# Pg4_Switches_Latches_Connectors.net
KiCad netlist of a schematic drawn in Altium Designer
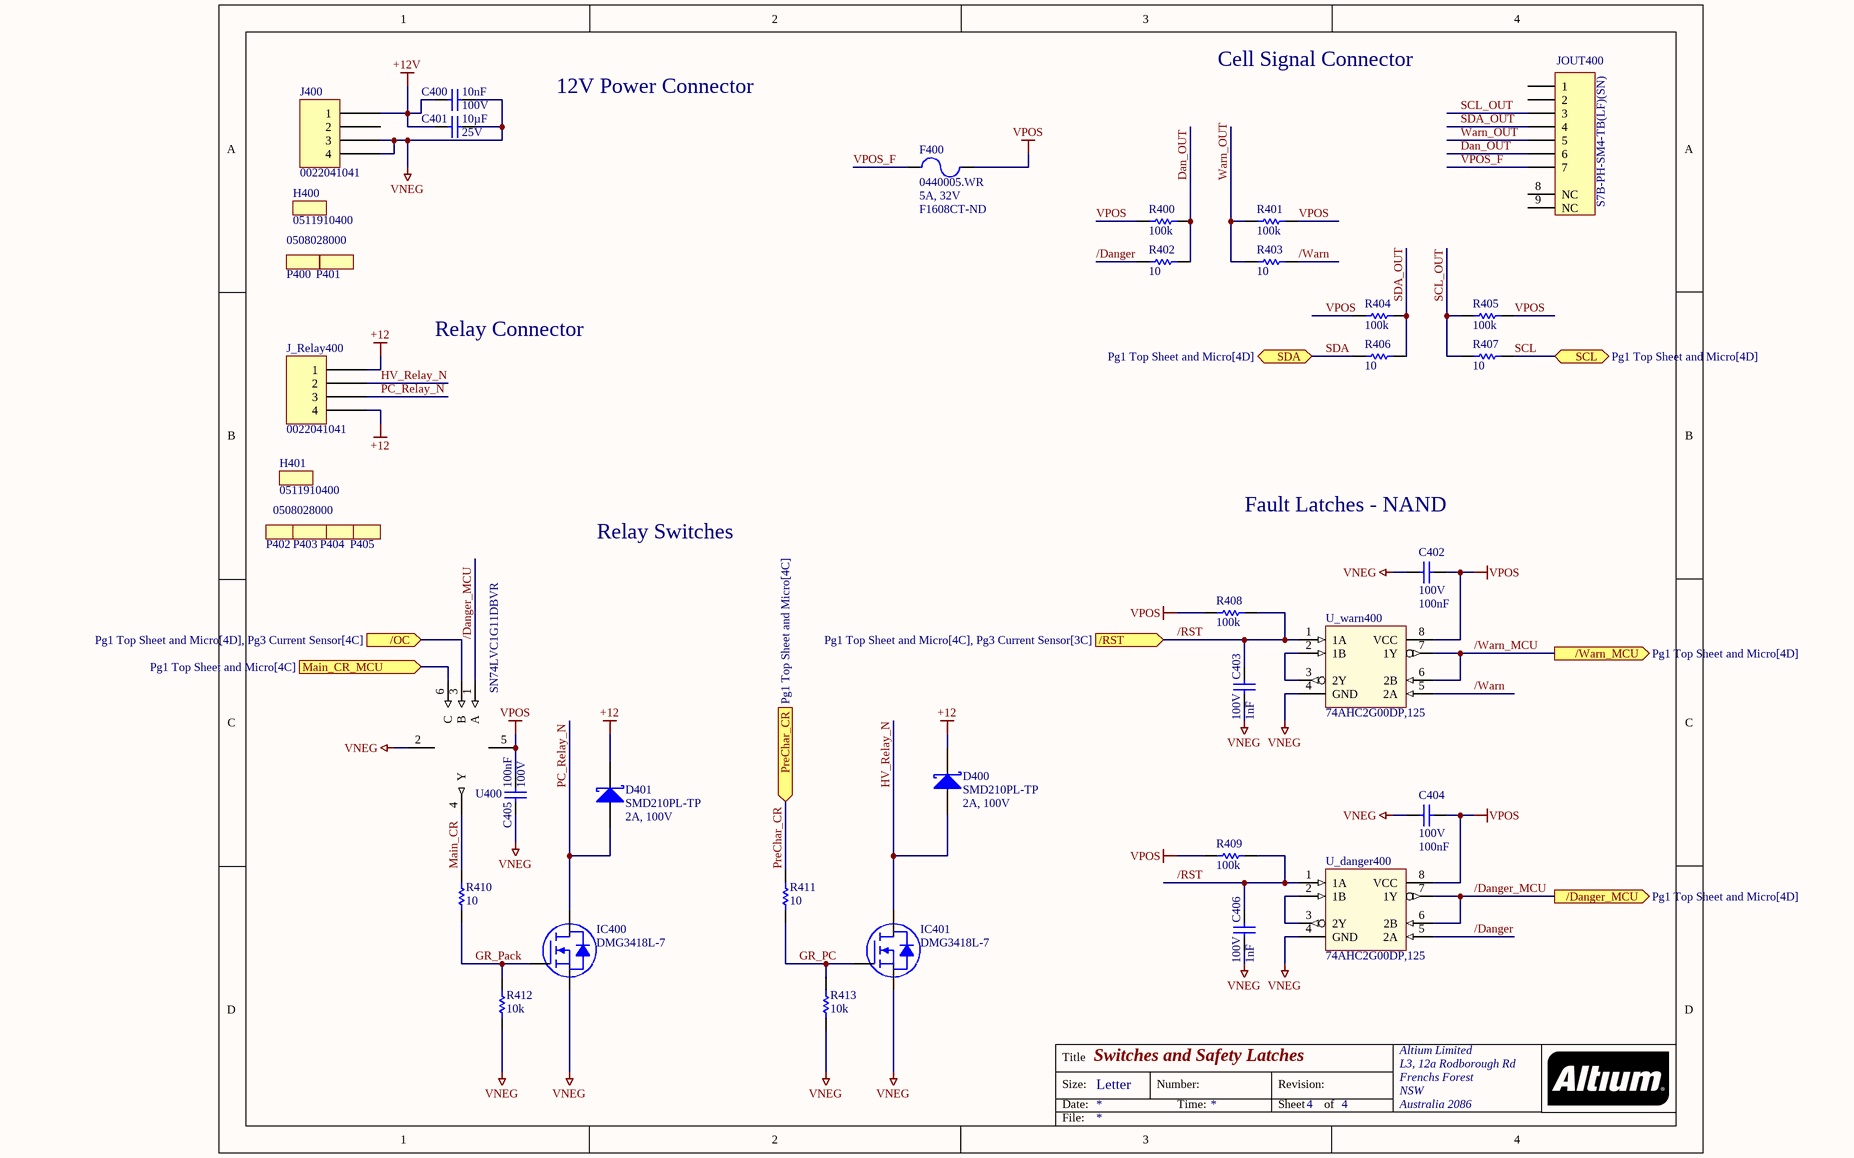
[diagram p0: Pg4 Switches, Latches, Connectors.SchDoc]

(export (version "E")
  (design (tool "Eeschema 10.0.6"))
  (components
    (comp (ref "C400")
      (value "10nF")
      (footprint "CAPC2012N")
      (description "Capacitor, Ceramic, 10nF, 100V, 0805, 10%, 125C")
      (fields (field (name "RATED") "100V") (field (name "Comment") "C0805C103K1RAC7025"))
      (libsource (lib "SchLib - EE391 Master") (part "C0805C103K1RAC7025"))
    )
    (comp (ref "C401")
      (value "10µF")
      (footprint "CAPC3225N")
      (description "Capacitor, Ceramic, 10µF, 25V, 0805, 10%, 125C")
      (fields (field (name "RATED") "25V") (field (name "Comment") "C1210C106K3RACAUTO"))
      (libsource (lib "SchLib - EE391 Master") (part "C1210C106K3RACAUTO"))
    )
    (comp (ref "C402")
      (value "100nF")
      (footprint "CAPC2012N")
      (description "Capacitor, Ceramic, 100nF, 25V, 0805, 10%, 125C")
      (fields (field (name "RATED") "100V") (field (name "Comment") "CL21B104KACNNNC"))
      (libsource (lib "SchLib - EE391 Master") (part "C0805C104K1RACAUTO"))
    )
    (comp (ref "C403")
      (value "1nF")
      (footprint "CAPC2012N")
      (description "Capacitor, Ceramic, 1nF, 100V, 0805, 10%, 125C")
      (fields (field (name "RATED") "100V") (field (name "Comment") "C0805C102K1RACAUTO"))
      (libsource (lib "SchLib - EE391 Master") (part "C0805C102K1RACAUTO"))
    )
    (comp (ref "C404")
      (value "100nF")
      (footprint "CAPC2012N")
      (description "Capacitor, Ceramic, 100nF, 25V, 0805, 10%, 125C")
      (fields (field (name "RATED") "100V") (field (name "Comment") "CL21B104KACNNNC"))
      (libsource (lib "SchLib - EE391 Master") (part "C0805C104K1RACAUTO"))
    )
    (comp (ref "C405")
      (value "100nF")
      (footprint "CAPC2012N")
      (description "Capacitor, Ceramic, 100nF, 25V, 0805, 10%, 125C")
      (fields (field (name "RATED") "100V") (field (name "Comment") "CL21B104KACNNNC"))
      (libsource (lib "SchLib - EE391 Master") (part "C0805C104K1RACAUTO"))
    )
    (comp (ref "C406")
      (value "1nF")
      (footprint "CAPC2012N")
      (description "Capacitor, Ceramic, 1nF, 100V, 0805, 10%, 125C")
      (fields (field (name "RATED") "100V") (field (name "Comment") "C0805C102K1RACAUTO"))
      (libsource (lib "SchLib - EE391 Master") (part "C0805C102K1RACAUTO"))
    )
    (comp (ref "D400")
      (value "SMD210PL-TP")
      (footprint "SOD123")
      (description "Diode, Si Sch, 100V, 2A, SOD123")
      (fields (field (name "RATED") "2A, 100V"))
      (libsource (lib "SchLib - EE391 Master") (part "SMD210PL"))
    )
    (comp (ref "D401")
      (value "SMD210PL-TP")
      (footprint "SOD123")
      (description "Diode, Si Sch, 100V, 2A, SOD123")
      (fields (field (name "RATED") "2A, 100V"))
      (libsource (lib "SchLib - EE391 Master") (part "SMD210PL"))
    )
    (comp (ref "F400")
      (value "0440005.WR")
      (footprint "CAPC1608N")
      (description "Fuse, SMT, 5A, 32VAC/VDC, 1206")
      (fields (field (name "RATED") "5A, 32V") (field (name "SUPPLIER PART NUMBER 1") "F1608CT-ND"))
      (libsource (lib "SchLib - EE391 Master") (part "0440005.WR"))
    )
    (comp (ref "H400")
      (value "0511910400")
      (description "Housing, Molex, Maiting Part 0511910400")
      (libsource (lib "Connectors") (part "0022041041(Housing)"))
    )
    (comp (ref "H401")
      (value "0511910400")
      (description "Housing, Molex, Maiting Part 0511910400")
      (libsource (lib "Connectors") (part "0022041041(Housing)"))
    )
    (comp (ref "IC400")
      (value "DMG3418L-7")
      (footprint "DIODES SOT-23-3")
      (description "MOSFET N-CH 30V 4A SOT23")
      (fields (field (name "MANUFACTURER") "Diodes Incorporated"))
      (libsource (lib "Celestial Altium Library - altium_library") (part "DIODES INC MOSFET N-CH SOT-23-3"))
    )
    (comp (ref "IC401")
      (value "DMG3418L-7")
      (footprint "DIODES SOT-23-3")
      (description "MOSFET N-CH 30V 4A SOT23")
      (fields (field (name "MANUFACTURER") "Diodes Incorporated"))
      (libsource (lib "Celestial Altium Library - altium_library") (part "DIODES INC MOSFET N-CH SOT-23-3"))
    )
    (comp (ref "J400")
      (value "0022041041")
      (footprint "0022041041")
      (description "Header, 4 pos, 2.5mm pitch, Molex\r\nKit Parts\r\nHousing: 0511910400\r\nTerminals: 0508028000")
      (libsource (lib "Connectors") (part "0022041041"))
    )
    (comp (ref "JOUT400")
      (value "S7B-PH-SM4-TB(LF)(SN)")
      (footprint "JST-PH-S7")
      (description "Header, JST, 7-Pin, Right-Angle, PH, Surface Mount")
      (libsource (lib "SchLib - EE391 Master") (part "S7B-PH-SM4-TB(LF)(SN)"))
    )
    (comp (ref "J_Relay400")
      (value "0022041041")
      (footprint "0022041041")
      (description "Header, 4 pos, 2.5mm pitch, Molex\r\nKit Parts\r\nHousing: 0511910400\r\nTerminals: 0508028000")
      (libsource (lib "Connectors") (part "0022041041"))
    )
    (comp (ref "P400")
      (value "0508028000")
      (description "Terminal, Molex, Maiting Part 0511910400")
      (libsource (lib "Connectors") (part "0022041041(Terminal)"))
    )
    (comp (ref "P401")
      (value "0508028000")
      (description "Terminal, Molex, Maiting Part 0511910400")
      (libsource (lib "") (part "0022041041(Terminal)_1"))
    )
    (comp (ref "P402")
      (value "0508028000")
      (description "Terminal, Molex, Maiting Part 0511910400")
      (libsource (lib "") (part "0022041041(Terminal)_1"))
    )
    (comp (ref "P403")
      (value "0508028000")
      (description "Terminal, Molex, Maiting Part 0511910400")
      (libsource (lib "") (part "0022041041(Terminal)_1"))
    )
    (comp (ref "P404")
      (value "0508028000")
      (description "Terminal, Molex, Maiting Part 0511910400")
      (libsource (lib "") (part "0022041041(Terminal)_1"))
    )
    (comp (ref "P405")
      (value "0508028000")
      (description "Terminal, Molex, Maiting Part 0511910400")
      (libsource (lib "") (part "0022041041(Terminal)_1"))
    )
    (comp (ref "R400")
      (value "100k")
      (footprint "RESC2012N")
      (description "Resistor, Fixed, 100 kOhm, 0805, 1%, 1/8W")
      (fields (field (name "Comment") "ERJ-6ENF1003V"))
      (libsource (lib "SchLib - EE391 Master") (part "ERJ-6ENF1003V"))
    )
    (comp (ref "R401")
      (value "100k")
      (footprint "RESC2012N")
      (description "Resistor, Fixed, 100 kOhm, 0805, 1%, 1/8W")
      (fields (field (name "Comment") "ERJ-6ENF1003V"))
      (libsource (lib "SchLib - EE391 Master") (part "ERJ-6ENF1003V"))
    )
    (comp (ref "R402")
      (value "10")
      (footprint "RESC2012N")
      (description "Resistor, Fixed, 10 Ohm, 0805, 1%, 1/8W")
      (fields (field (name "Comment") "ERJ-6ENF10R0V"))
      (libsource (lib "SchLib - EE391 Master") (part "ERJ-6ENF10R0V"))
    )
    (comp (ref "R403")
      (value "10")
      (footprint "RESC2012N")
      (description "Resistor, Fixed, 10 Ohm, 0805, 1%, 1/8W")
      (fields (field (name "Comment") "ERJ-6ENF10R0V"))
      (libsource (lib "SchLib - EE391 Master") (part "ERJ-6ENF10R0V"))
    )
    (comp (ref "R404")
      (value "100k")
      (footprint "RESC2012N")
      (description "Resistor, Fixed, 100 kOhm, 0805, 1%, 1/8W")
      (fields (field (name "Comment") "ERJ-6ENF1003V"))
      (libsource (lib "SchLib - EE391 Master") (part "ERJ-6ENF1003V"))
    )
    (comp (ref "R405")
      (value "100k")
      (footprint "RESC2012N")
      (description "Resistor, Fixed, 100 kOhm, 0805, 1%, 1/8W")
      (fields (field (name "Comment") "ERJ-6ENF1003V"))
      (libsource (lib "SchLib - EE391 Master") (part "ERJ-6ENF1003V"))
    )
    (comp (ref "R406")
      (value "10")
      (footprint "RESC2012N")
      (description "Resistor, Fixed, 10 Ohm, 0805, 1%, 1/8W")
      (fields (field (name "Comment") "ERJ-6ENF10R0V"))
      (libsource (lib "SchLib - EE391 Master") (part "ERJ-6ENF10R0V"))
    )
    (comp (ref "R407")
      (value "10")
      (footprint "RESC2012N")
      (description "Resistor, Fixed, 10 Ohm, 0805, 1%, 1/8W")
      (fields (field (name "Comment") "ERJ-6ENF10R0V"))
      (libsource (lib "SchLib - EE391 Master") (part "ERJ-6ENF10R0V"))
    )
    (comp (ref "R408")
      (value "100k")
      (footprint "RESC2012N")
      (description "Resistor, Fixed, 100 kOhm, 0805, 1%, 1/8W")
      (fields (field (name "Comment") "ERJ-6ENF1003V"))
      (libsource (lib "SchLib - EE391 Master") (part "ERJ-6ENF1003V"))
    )
    (comp (ref "R409")
      (value "100k")
      (footprint "RESC2012N")
      (description "Resistor, Fixed, 100 kOhm, 0805, 1%, 1/8W")
      (fields (field (name "Comment") "ERJ-6ENF1003V"))
      (libsource (lib "SchLib - EE391 Master") (part "ERJ-6ENF1003V"))
    )
    (comp (ref "R410")
      (value "10")
      (footprint "RESC2012N")
      (description "Resistor, Fixed, 10 Ohm, 0805, 1%, 1/8W")
      (fields (field (name "Comment") "ERJ-6ENF10R0V"))
      (libsource (lib "SchLib - EE391 Master") (part "ERJ-6ENF10R0V"))
    )
    (comp (ref "R411")
      (value "10")
      (footprint "RESC2012N")
      (description "Resistor, Fixed, 10 Ohm, 0805, 1%, 1/8W")
      (fields (field (name "Comment") "ERJ-6ENF10R0V"))
      (libsource (lib "SchLib - EE391 Master") (part "ERJ-6ENF10R0V"))
    )
    (comp (ref "R412")
      (value "10k")
      (footprint "RESC2012N")
      (description "Resistor, Fixed, 10 kOhm, 0805, 1%, 1/8W")
      (fields (field (name "Comment") "ERJ-6ENF1002V"))
      (libsource (lib "SchLib - EE391 Master") (part "ERJ-6ENF1002V"))
    )
    (comp (ref "R413")
      (value "10k")
      (footprint "RESC2012N")
      (description "Resistor, Fixed, 10 kOhm, 0805, 1%, 1/8W")
      (fields (field (name "Comment") "ERJ-6ENF1002V"))
      (libsource (lib "SchLib - EE391 Master") (part "ERJ-6ENF1002V"))
    )
    (comp (ref "U400")
      (value "SN74LVC1G11DBVR")
      (footprint "SOT23-6N")
      (description "Logic, AND, Single, 3-In, SOT23-6")
      (libsource (lib "SchLib - EE391 Master") (part "74LVC1G11"))
    )
    (comp (ref "U_danger400")
      (value "74AHC2G00DP,125")
      (footprint "TSSOP-8")
      (description "Logic, NAND, Dual, Schmitt Trigger, TSSOP-8")
      (libsource (lib "SchLib - EE391 Master") (part "74AHC2G00"))
    )
    (comp (ref "U_warn400")
      (value "74AHC2G00DP,125")
      (footprint "TSSOP-8")
      (description "Logic, NAND, Dual, Schmitt Trigger, TSSOP-8")
      (libsource (lib "SchLib - EE391 Master") (part "74AHC2G00"))
    )
  )
  (nets
    (net (code "1") (name "+12") (class "Default")
      (node (ref "D400") (pin "2") (pinfunction "K_2") (pintype "passive"))
      (node (ref "D401") (pin "2") (pinfunction "K_2") (pintype "passive"))
      (node (ref "J_Relay400") (pin "1") (pinfunction "1_1") (pintype "passive"))
      (node (ref "J_Relay400") (pin "4") (pinfunction "4_4") (pintype "passive"))
    )
    (net (code "2") (name "+12V") (class "Default")
      (node (ref "C400") (pin "1") (pinfunction "1_1") (pintype "passive"))
      (node (ref "C401") (pin "1") (pinfunction "1_1") (pintype "passive"))
      (node (ref "J400") (pin "1") (pinfunction "1_1") (pintype "passive"))
    )
    (net (code "3") (name "/Dan_OUT") (class "Default")
      (node (ref "JOUT400") (pin "6") (pinfunction "6_6") (pintype "passive"))
      (node (ref "R400") (pin "1") (pinfunction "1_1") (pintype "passive"))
      (node (ref "R402") (pin "2") (pinfunction "2_2") (pintype "passive"))
    )
    (net (code "4") (name "/GR_PC") (class "Default")
      (node (ref "IC401") (pin "1") (pinfunction "G_1") (pintype "passive"))
      (node (ref "R411") (pin "1") (pinfunction "1_1") (pintype "passive"))
      (node (ref "R413") (pin "2") (pinfunction "2_2") (pintype "passive"))
    )
    (net (code "5") (name "/GR_Pack") (class "Default")
      (node (ref "IC400") (pin "1") (pinfunction "G_1") (pintype "passive"))
      (node (ref "R410") (pin "1") (pinfunction "1_1") (pintype "passive"))
      (node (ref "R412") (pin "2") (pinfunction "2_2") (pintype "passive"))
    )
    (net (code "6") (name "/HV_Relay_N") (class "Default")
      (node (ref "D400") (pin "1") (pinfunction "A_1") (pintype "passive"))
      (node (ref "IC401") (pin "3") (pinfunction "D_3") (pintype "passive"))
      (node (ref "J_Relay400") (pin "2") (pinfunction "2_2") (pintype "passive"))
    )
    (net (code "7") (name "/Main_CR") (class "Default")
      (node (ref "R410") (pin "2") (pinfunction "2_2") (pintype "passive"))
      (node (ref "U400") (pin "4") (pinfunction "Y_4") (pintype "output"))
    )
    (net (code "8") (name "/Main_CR_MCU") (class "Default")
      (node (ref "U400") (pin "6") (pinfunction "C_6") (pintype "input"))
    )
    (net (code "9") (name "/PC_Relay_N") (class "Default")
      (node (ref "D401") (pin "1") (pinfunction "A_1") (pintype "passive"))
      (node (ref "IC400") (pin "3") (pinfunction "D_3") (pintype "passive"))
      (node (ref "J_Relay400") (pin "3") (pinfunction "3_3") (pintype "passive"))
    )
    (net (code "10") (name "/PreChar_CR") (class "Default")
      (node (ref "R411") (pin "2") (pinfunction "2_2") (pintype "passive"))
    )
    (net (code "11") (name "/SCL") (class "Default")
      (node (ref "R407") (pin "2") (pinfunction "2_2") (pintype "passive"))
    )
    (net (code "12") (name "/SCL_OUT") (class "Default")
      (node (ref "JOUT400") (pin "3") (pinfunction "3_3") (pintype "passive"))
      (node (ref "R405") (pin "2") (pinfunction "2_2") (pintype "passive"))
      (node (ref "R407") (pin "1") (pinfunction "1_1") (pintype "passive"))
    )
    (net (code "13") (name "/SDA") (class "Default")
      (node (ref "R406") (pin "1") (pinfunction "1_1") (pintype "passive"))
    )
    (net (code "14") (name "/SDA_OUT") (class "Default")
      (node (ref "JOUT400") (pin "4") (pinfunction "4_4") (pintype "passive"))
      (node (ref "R404") (pin "1") (pinfunction "1_1") (pintype "passive"))
      (node (ref "R406") (pin "2") (pinfunction "2_2") (pintype "passive"))
    )
    (net (code "15") (name "/VPOS_F") (class "Default")
      (node (ref "F400") (pin "1") (pinfunction "1_1") (pintype "passive"))
      (node (ref "JOUT400") (pin "7") (pinfunction "7_7") (pintype "passive"))
    )
    (net (code "16") (name "/Warn_OUT") (class "Default")
      (node (ref "JOUT400") (pin "5") (pinfunction "5_5") (pintype "passive"))
      (node (ref "R401") (pin "2") (pinfunction "2_2") (pintype "passive"))
      (node (ref "R403") (pin "1") (pinfunction "1_1") (pintype "passive"))
    )
    (net (code "17") (name "/{slash}Danger") (class "Default")
      (node (ref "R402") (pin "1") (pinfunction "1_1") (pintype "passive"))
      (node (ref "U_danger400") (pin "5") (pinfunction "2A_5") (pintype "input"))
    )
    (net (code "18") (name "/{slash}Danger_MCU") (class "Default")
      (node (ref "U400") (pin "1") (pinfunction "A_1") (pintype "input"))
      (node (ref "U_danger400") (pin "6") (pinfunction "2B_6") (pintype "input"))
      (node (ref "U_danger400") (pin "7") (pinfunction "1Y_7") (pintype "output"))
    )
    (net (code "19") (name "/{slash}OC") (class "Default")
      (node (ref "U400") (pin "3") (pinfunction "B_3") (pintype "input"))
    )
    (net (code "20") (name "/{slash}RST") (class "Default")
      (node (ref "C403") (pin "1") (pinfunction "1_1") (pintype "passive"))
      (node (ref "C406") (pin "1") (pinfunction "1_1") (pintype "passive"))
      (node (ref "R408") (pin "1") (pinfunction "1_1") (pintype "passive"))
      (node (ref "R409") (pin "1") (pinfunction "1_1") (pintype "passive"))
      (node (ref "U_danger400") (pin "1") (pinfunction "1A_1") (pintype "input"))
      (node (ref "U_warn400") (pin "1") (pinfunction "1A_1") (pintype "input"))
    )
    (net (code "21") (name "/{slash}Warn") (class "Default")
      (node (ref "R403") (pin "2") (pinfunction "2_2") (pintype "passive"))
      (node (ref "U_warn400") (pin "5") (pinfunction "2A_5") (pintype "input"))
    )
    (net (code "22") (name "/{slash}Warn_MCU") (class "Default")
      (node (ref "U_warn400") (pin "6") (pinfunction "2B_6") (pintype "input"))
      (node (ref "U_warn400") (pin "7") (pinfunction "1Y_7") (pintype "output"))
    )
    (net (code "23") (name "Net-(U_danger400-1B)") (class "Default")
      (node (ref "U_danger400") (pin "2") (pinfunction "1B_2") (pintype "input"))
      (node (ref "U_danger400") (pin "3") (pinfunction "2Y_3") (pintype "output"))
    )
    (net (code "24") (name "Net-(U_warn400-1B)") (class "Default")
      (node (ref "U_warn400") (pin "2") (pinfunction "1B_2") (pintype "input"))
      (node (ref "U_warn400") (pin "3") (pinfunction "2Y_3") (pintype "output"))
    )
    (net (code "25") (name "VNEG") (class "Default")
      (node (ref "C400") (pin "2") (pinfunction "2_2") (pintype "passive"))
      (node (ref "C401") (pin "2") (pinfunction "2_2") (pintype "passive"))
      (node (ref "C402") (pin "2") (pinfunction "2_2") (pintype "passive"))
      (node (ref "C403") (pin "2") (pinfunction "2_2") (pintype "passive"))
      (node (ref "C404") (pin "2") (pinfunction "2_2") (pintype "passive"))
      (node (ref "C405") (pin "2") (pinfunction "2_2") (pintype "passive"))
      (node (ref "C406") (pin "2") (pinfunction "2_2") (pintype "passive"))
      (node (ref "IC400") (pin "2") (pinfunction "S_2") (pintype "passive"))
      (node (ref "IC401") (pin "2") (pinfunction "S_2") (pintype "passive"))
      (node (ref "J400") (pin "3") (pinfunction "3_3") (pintype "passive"))
      (node (ref "J400") (pin "4") (pinfunction "4_4") (pintype "passive"))
      (node (ref "R412") (pin "1") (pinfunction "1_1") (pintype "passive"))
      (node (ref "R413") (pin "1") (pinfunction "1_1") (pintype "passive"))
      (node (ref "U400") (pin "2") (pinfunction "GND_2") (pintype "power_in"))
      (node (ref "U_danger400") (pin "4") (pinfunction "GND_4") (pintype "power_in"))
      (node (ref "U_warn400") (pin "4") (pinfunction "GND_4") (pintype "power_in"))
    )
    (net (code "26") (name "VPOS") (class "Default")
      (node (ref "C402") (pin "1") (pinfunction "1_1") (pintype "passive"))
      (node (ref "C404") (pin "1") (pinfunction "1_1") (pintype "passive"))
      (node (ref "C405") (pin "1") (pinfunction "1_1") (pintype "passive"))
      (node (ref "F400") (pin "2") (pinfunction "2_2") (pintype "passive"))
      (node (ref "R400") (pin "2") (pinfunction "2_2") (pintype "passive"))
      (node (ref "R401") (pin "1") (pinfunction "1_1") (pintype "passive"))
      (node (ref "R404") (pin "2") (pinfunction "2_2") (pintype "passive"))
      (node (ref "R405") (pin "1") (pinfunction "1_1") (pintype "passive"))
      (node (ref "R408") (pin "2") (pinfunction "2_2") (pintype "passive"))
      (node (ref "R409") (pin "2") (pinfunction "2_2") (pintype "passive"))
      (node (ref "U400") (pin "5") (pinfunction "VCC_5") (pintype "power_in"))
      (node (ref "U_danger400") (pin "8") (pinfunction "VCC_8") (pintype "power_in"))
      (node (ref "U_warn400") (pin "8") (pinfunction "VCC_8") (pintype "power_in"))
    )
    (net (code "27") (name "unconnected-(J400-Pad2)") (class "Default")
      (node (ref "J400") (pin "2") (pinfunction "2_2") (pintype "passive"))
    )
    (net (code "28") (name "unconnected-(JOUT400-NC-Pad8)") (class "Default")
      (node (ref "JOUT400") (pin "8") (pinfunction "NC_8") (pintype "tri_state"))
    )
    (net (code "29") (name "unconnected-(JOUT400-NC-Pad9)") (class "Default")
      (node (ref "JOUT400") (pin "9") (pinfunction "NC_9") (pintype "tri_state"))
    )
    (net (code "30") (name "unconnected-(JOUT400-Pad1)") (class "Default")
      (node (ref "JOUT400") (pin "1") (pinfunction "1_1") (pintype "passive"))
    )
    (net (code "31") (name "unconnected-(JOUT400-Pad2)") (class "Default")
      (node (ref "JOUT400") (pin "2") (pinfunction "2_2") (pintype "passive"))
    )
  )
)
